# SheetPower.net
KiCad netlist of a schematic drawn in Altium Designer
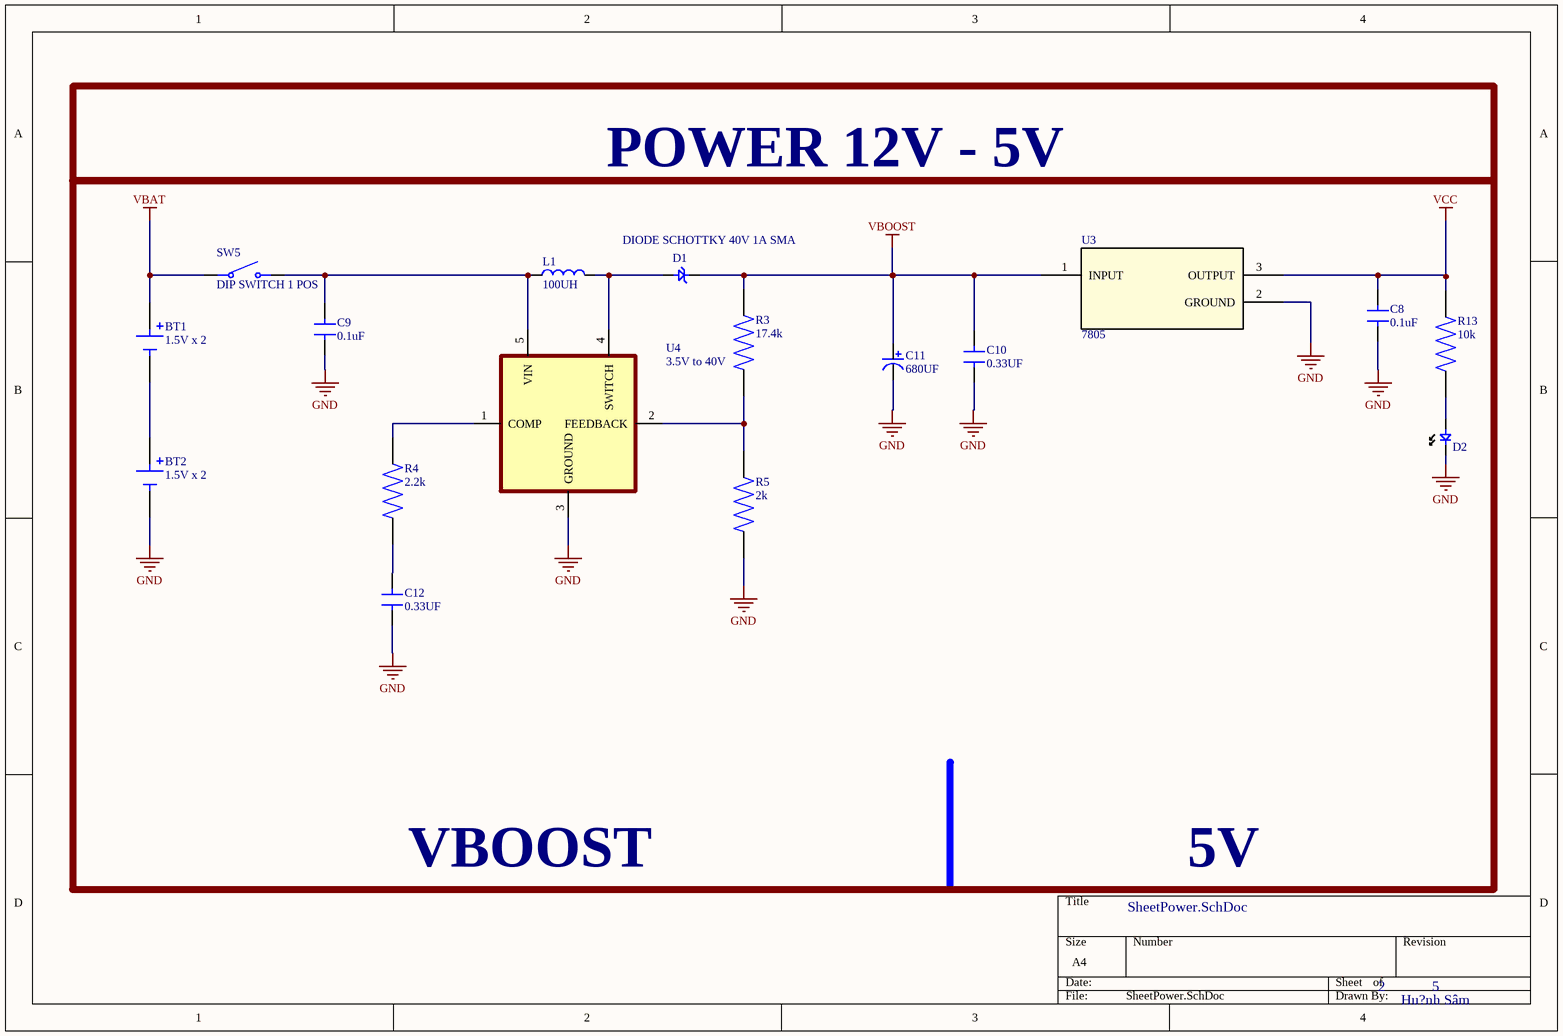
[diagram p0: SheetPower.SchDoc]

(export (version "E")
  (design (tool "Eeschema 10.0.6"))
  (components
    (comp (ref "BT1")
      (value "1.5V x 2")
      (footprint "AAA battery holder")
      (description "2 AAA Battery Holder")
      (fields (field (name "MP") "BC2AAAL"))
      (libsource (lib "SchlibRobotLine") (part "BC2AAAL"))
    )
    (comp (ref "BT2")
      (value "1.5V x 2")
      (footprint "AAA battery holder")
      (description "2 AAA Battery Holder")
      (fields (field (name "MP") "BC2AAAL"))
      (libsource (lib "SchlibRobotLine") (part "BC2AAAL"))
    )
    (comp (ref "C8")
      (value "0.1uF")
      (footprint "CAP104 0.1UF 50V")
      (description "Cap Ceramic 0.1uF 50V X7R 10% SMD 2.0 x 1.2 mm 125 C Paper T/R")
      (fields
        (field (name "MANUFACTURER") "KEMET")
        (field (name "MANUFACTURER PART NUMBER") "C0805C104K5RACTU")
      )
      (libsource (lib "SchlibRobotLine") (part "C0805C104K5RACTU"))
    )
    (comp (ref "C9")
      (value "0.1uF")
      (footprint "CAP104 0.1UF 50V")
      (description "Cap Ceramic 0.1uF 50V X7R 10% SMD 2.0 x 1.2 mm 125 C Paper T/R")
      (fields
        (field (name "MANUFACTURER") "KEMET")
        (field (name "MANUFACTURER PART NUMBER") "C0805C104K5RACTU")
      )
      (libsource (lib "SchlibRobotLine") (part "C0805C104K5RACTU"))
    )
    (comp (ref "C10")
      (value "0.33UF")
      (footprint "CAP 0.33UF")
      (description "Multilayer Ceramic Capacitors MLCC - SMD/SMT 16volts 0.33uF Y5V 20%")
      (fields
        (field (name "MANUFACTURER") "KEMET")
        (field (name "MANUFACTURER PART NUMBER") "C0805C334M4VACTU")
      )
      (libsource (lib "SchlibRobotLine") (part "C0805C334M4VACTU"))
    )
    (comp (ref "C11")
      (value "680UF")
      (footprint "680uf 35v")
      (description "Cap Alum 680UF 20% 35V SMD")
      (fields
        (field (name "MANUFACTURER") "Nichicon")
        (field (name "MANUFACTURER PART NUMBER") "UCX1V681MNS1MS")
      )
      (libsource (lib "SchlibRobotLine") (part "UCX1V681MNS1MS"))
    )
    (comp (ref "C12")
      (value "0.33UF")
      (footprint "CAP 0.33UF")
      (description "Multilayer Ceramic Capacitors MLCC - SMD/SMT 16volts 0.33uF Y5V 20%")
      (fields
        (field (name "MANUFACTURER") "KEMET")
        (field (name "MANUFACTURER PART NUMBER") "C0805C334M4VACTU")
      )
      (libsource (lib "SchlibRobotLine") (part "C0805C334M4VACTU"))
    )
    (comp (ref "D1")
      (value "DIODE SCHOTTKY 40V 1A SMA")
      (footprint "DIODE SCHOTTKY 40V 1A SMA")
      (description "ON SEMICONDUCTOR - SS14 - DIODE, SCHOTTKY, 1A, 40V, DO-214AC-2")
      (fields
        (field (name "MANUFACTURER") "ON Semiconductor / Fairchild")
        (field (name "MANUFACTURER PART NUMBER") "SS14")
      )
      (libsource (lib "SchlibRobotLine") (part "SS14"))
    )
    (comp (ref "D2")
      (value "LED SM 0805 2V 100MCD RED")
      (footprint "LED 0805")
      (description "Red 625nm LED Indication - Discrete 2V 0805 (2012 Metric)")
      (fields
        (field (name "MANUFACTURER") "Visual Communications")
        (field (name "MANUFACTURER PART NUMBER") "LSM0805412V")
      )
      (libsource (lib "SchlibRobotLine") (part "LSM0805412V"))
    )
    (comp (ref "L1")
      (value "100UH")
      (footprint "FIXED IND 100UH 2.5A 135MOHM SMD")
      (description "SMD Shieled Power Inductor;  100uH;  20%; SRR1210A")
      (fields
        (field (name "MANUFACTURER") "Bourns")
        (field (name "MANUFACTURER PART NUMBER") "SRR1210A-101M")
      )
      (libsource (lib "SchlibRobotLine") (part "SRR1210A-101M"))
    )
    (comp (ref "R3")
      (value "17.4k")
      (footprint "RESC2012X60N")
      (fields
        (field (name "MANUFACTURER") "Yageo")
        (field (name "MANUFACTURER PART NUMBER") "RC0805FR-0717K4L")
        (field (name "TOLERANCE") "1%")
      )
      (libsource (lib "SchlibRobotLine") (part "RC0805FR-0717K4L"))
    )
    (comp (ref "R4")
      (value "2.2k")
      (footprint "RESC2012X60N")
      (description "Res Thick Film 0805 2.2K Ohm 5% 0.125W(1/8W) ±100ppm/C Epoxy Pad SMD T/R")
      (fields
        (field (name "MANUFACTURER") "Yageo")
        (field (name "MANUFACTURER PART NUMBER") "RC0805JR-072K2L")
      )
      (libsource (lib "SchlibRobotLine") (part "RC0805JR-072K2L"))
    )
    (comp (ref "R5")
      (value "2k")
      (footprint "RESC2012X60N")
      (description "Res Thick Film 2.0 x 1.2 mm 2K Ohm 1% 0.125W(1/8W) 100ppm/ C Molded SMD Paper T/R")
      (fields
        (field (name "MANUFACTURER") "Yageo")
        (field (name "MANUFACTURER PART NUMBER") "RC0805FR-072KL")
      )
      (libsource (lib "SchlibRobotLine") (part "RC0805FR-072KL"))
    )
    (comp (ref "R13")
      (value "10k")
      (footprint "RC0805 10K OHM 1% 1/8W")
      (description "RES SMD 10K OHM 1% 1/8W 0805")
      (fields
        (field (name "MANUFACTURER") "Yageo")
        (field (name "MANUFACTURER PART NUMBER") "RC0805FR-0710KL")
      )
      (libsource (lib "SchlibRobotLine") (part "RC0805FR-0710KL"))
    )
    (comp (ref "SW5")
      (value "DIP SWITCH 1 POS")
      (footprint "DIP SWITCH 1 POS")
      (fields
        (field (name "MANUFACTURER") "CIT Relay & Switch")
        (field (name "MANUFACTURER PART NUMBER") "KG01ET")
      )
      (libsource (lib "SchlibRobotLine") (part "KG01ET"))
    )
    (comp (ref "U3")
      (value "7805")
      (footprint "DPAK-3_ONS-M")
      (description "Standard Regulator Pos 5V 0.5A 3-Pin(2+Tab) DPAK T/R")
      (fields
        (field (name "MANUFACTURER") "ON Semiconductor")
        (field (name "MANUFACTURER PART NUMBER") "MC78M05CDTRKG")
      )
      (libsource (lib "SchlibRobotLine") (part "MC78M05CDTRKG"))
    )
    (comp (ref "U4")
      (value "3.5V to 40V")
      (footprint "LM2577S-ADJ")
      (description "Converter DC-DC Single Step Up 3.5V to 40V 6-Pin (5+Tab) TO-263 Rail")
      (fields
        (field (name "MANUFACTURER") "TI National Semiconductor")
        (field (name "MANUFACTURER PART NUMBER") "LM2577S-ADJ/NOPB")
      )
      (libsource (lib "SchlibRobotLine") (part "LM2577S-ADJ/NOPB"))
    )
  )
  (nets
    (net (code "1") (name "GND") (class "Default")
      (node (ref "BT2") (pin "2") (pinfunction "2_2") (pintype "passive"))
      (node (ref "C10") (pin "1") (pinfunction "1_1") (pintype "passive"))
      (node (ref "C11") (pin "2") (pinfunction "2_2") (pintype "passive"))
      (node (ref "C12") (pin "1") (pinfunction "1_1") (pintype "passive"))
      (node (ref "C8") (pin "1") (pinfunction "1_1") (pintype "passive"))
      (node (ref "C9") (pin "1") (pinfunction "1_1") (pintype "passive"))
      (node (ref "D2") (pin "K") (pinfunction "K_K") (pintype "passive"))
      (node (ref "R5") (pin "1") (pinfunction "1_1") (pintype "passive"))
      (node (ref "U3") (pin "2") (pinfunction "GROUND_2") (pintype "power_in"))
      (node (ref "U4") (pin "3") (pinfunction "GROUND_3") (pintype "power_in"))
    )
    (net (code "2") (name "Net-(BT1-Pad2)") (class "Default")
      (node (ref "BT1") (pin "2") (pinfunction "2_2") (pintype "passive"))
      (node (ref "BT2") (pin "1") (pinfunction "1_1") (pintype "passive"))
    )
    (net (code "3") (name "Net-(C12-Pad2)") (class "Default")
      (node (ref "C12") (pin "2") (pinfunction "2_2") (pintype "passive"))
      (node (ref "R4") (pin "1") (pinfunction "1_1") (pintype "passive"))
    )
    (net (code "4") (name "Net-(D2-PadA)") (class "Default")
      (node (ref "D2") (pin "A") (pinfunction "A_A") (pintype "passive"))
      (node (ref "R13") (pin "1") (pinfunction "1_1") (pintype "passive"))
    )
    (net (code "5") (name "Net-(U4-COMP)") (class "Default")
      (node (ref "R4") (pin "2") (pinfunction "2_2") (pintype "passive"))
      (node (ref "U4") (pin "1") (pinfunction "COMP_1") (pintype "passive"))
    )
    (net (code "6") (name "Net-(U4-FEEDBACK)") (class "Default")
      (node (ref "R3") (pin "1") (pinfunction "1_1") (pintype "passive"))
      (node (ref "R5") (pin "2") (pinfunction "2_2") (pintype "passive"))
      (node (ref "U4") (pin "2") (pinfunction "FEEDBACK_2") (pintype "passive"))
    )
    (net (code "7") (name "Net-(U4-SWITCH)") (class "Default")
      (node (ref "D1") (pin "1") (pinfunction "1_1") (pintype "passive"))
      (node (ref "L1") (pin "2") (pinfunction "2_2") (pintype "passive"))
      (node (ref "U4") (pin "4") (pinfunction "SWITCH_4") (pintype "passive"))
    )
    (net (code "8") (name "Net-(U4-VIN)") (class "Default")
      (node (ref "C9") (pin "2") (pinfunction "2_2") (pintype "passive"))
      (node (ref "L1") (pin "1") (pinfunction "1_1") (pintype "passive"))
      (node (ref "SW5") (pin "2") (pinfunction "2_2") (pintype "passive"))
      (node (ref "U4") (pin "5") (pinfunction "VIN_5") (pintype "passive"))
    )
    (net (code "9") (name "VBAT") (class "Default")
      (node (ref "BT1") (pin "1") (pinfunction "1_1") (pintype "passive"))
      (node (ref "SW5") (pin "1") (pinfunction "1_1") (pintype "passive"))
    )
    (net (code "10") (name "VBOOST") (class "Default")
      (node (ref "C10") (pin "2") (pinfunction "2_2") (pintype "passive"))
      (node (ref "C11") (pin "1") (pinfunction "1_1") (pintype "passive"))
      (node (ref "D1") (pin "2") (pinfunction "2_2") (pintype "passive"))
      (node (ref "R3") (pin "2") (pinfunction "2_2") (pintype "passive"))
      (node (ref "U3") (pin "1") (pinfunction "INPUT_1") (pintype "passive"))
    )
    (net (code "11") (name "VCC") (class "Default")
      (node (ref "C8") (pin "2") (pinfunction "2_2") (pintype "passive"))
      (node (ref "R13") (pin "2") (pinfunction "2_2") (pintype "passive"))
      (node (ref "U3") (pin "3") (pinfunction "OUTPUT_3") (pintype "passive"))
    )
  )
)
